# Mechanical_and_Interconnect.net
KiCad netlist of a schematic drawn in Altium Designer
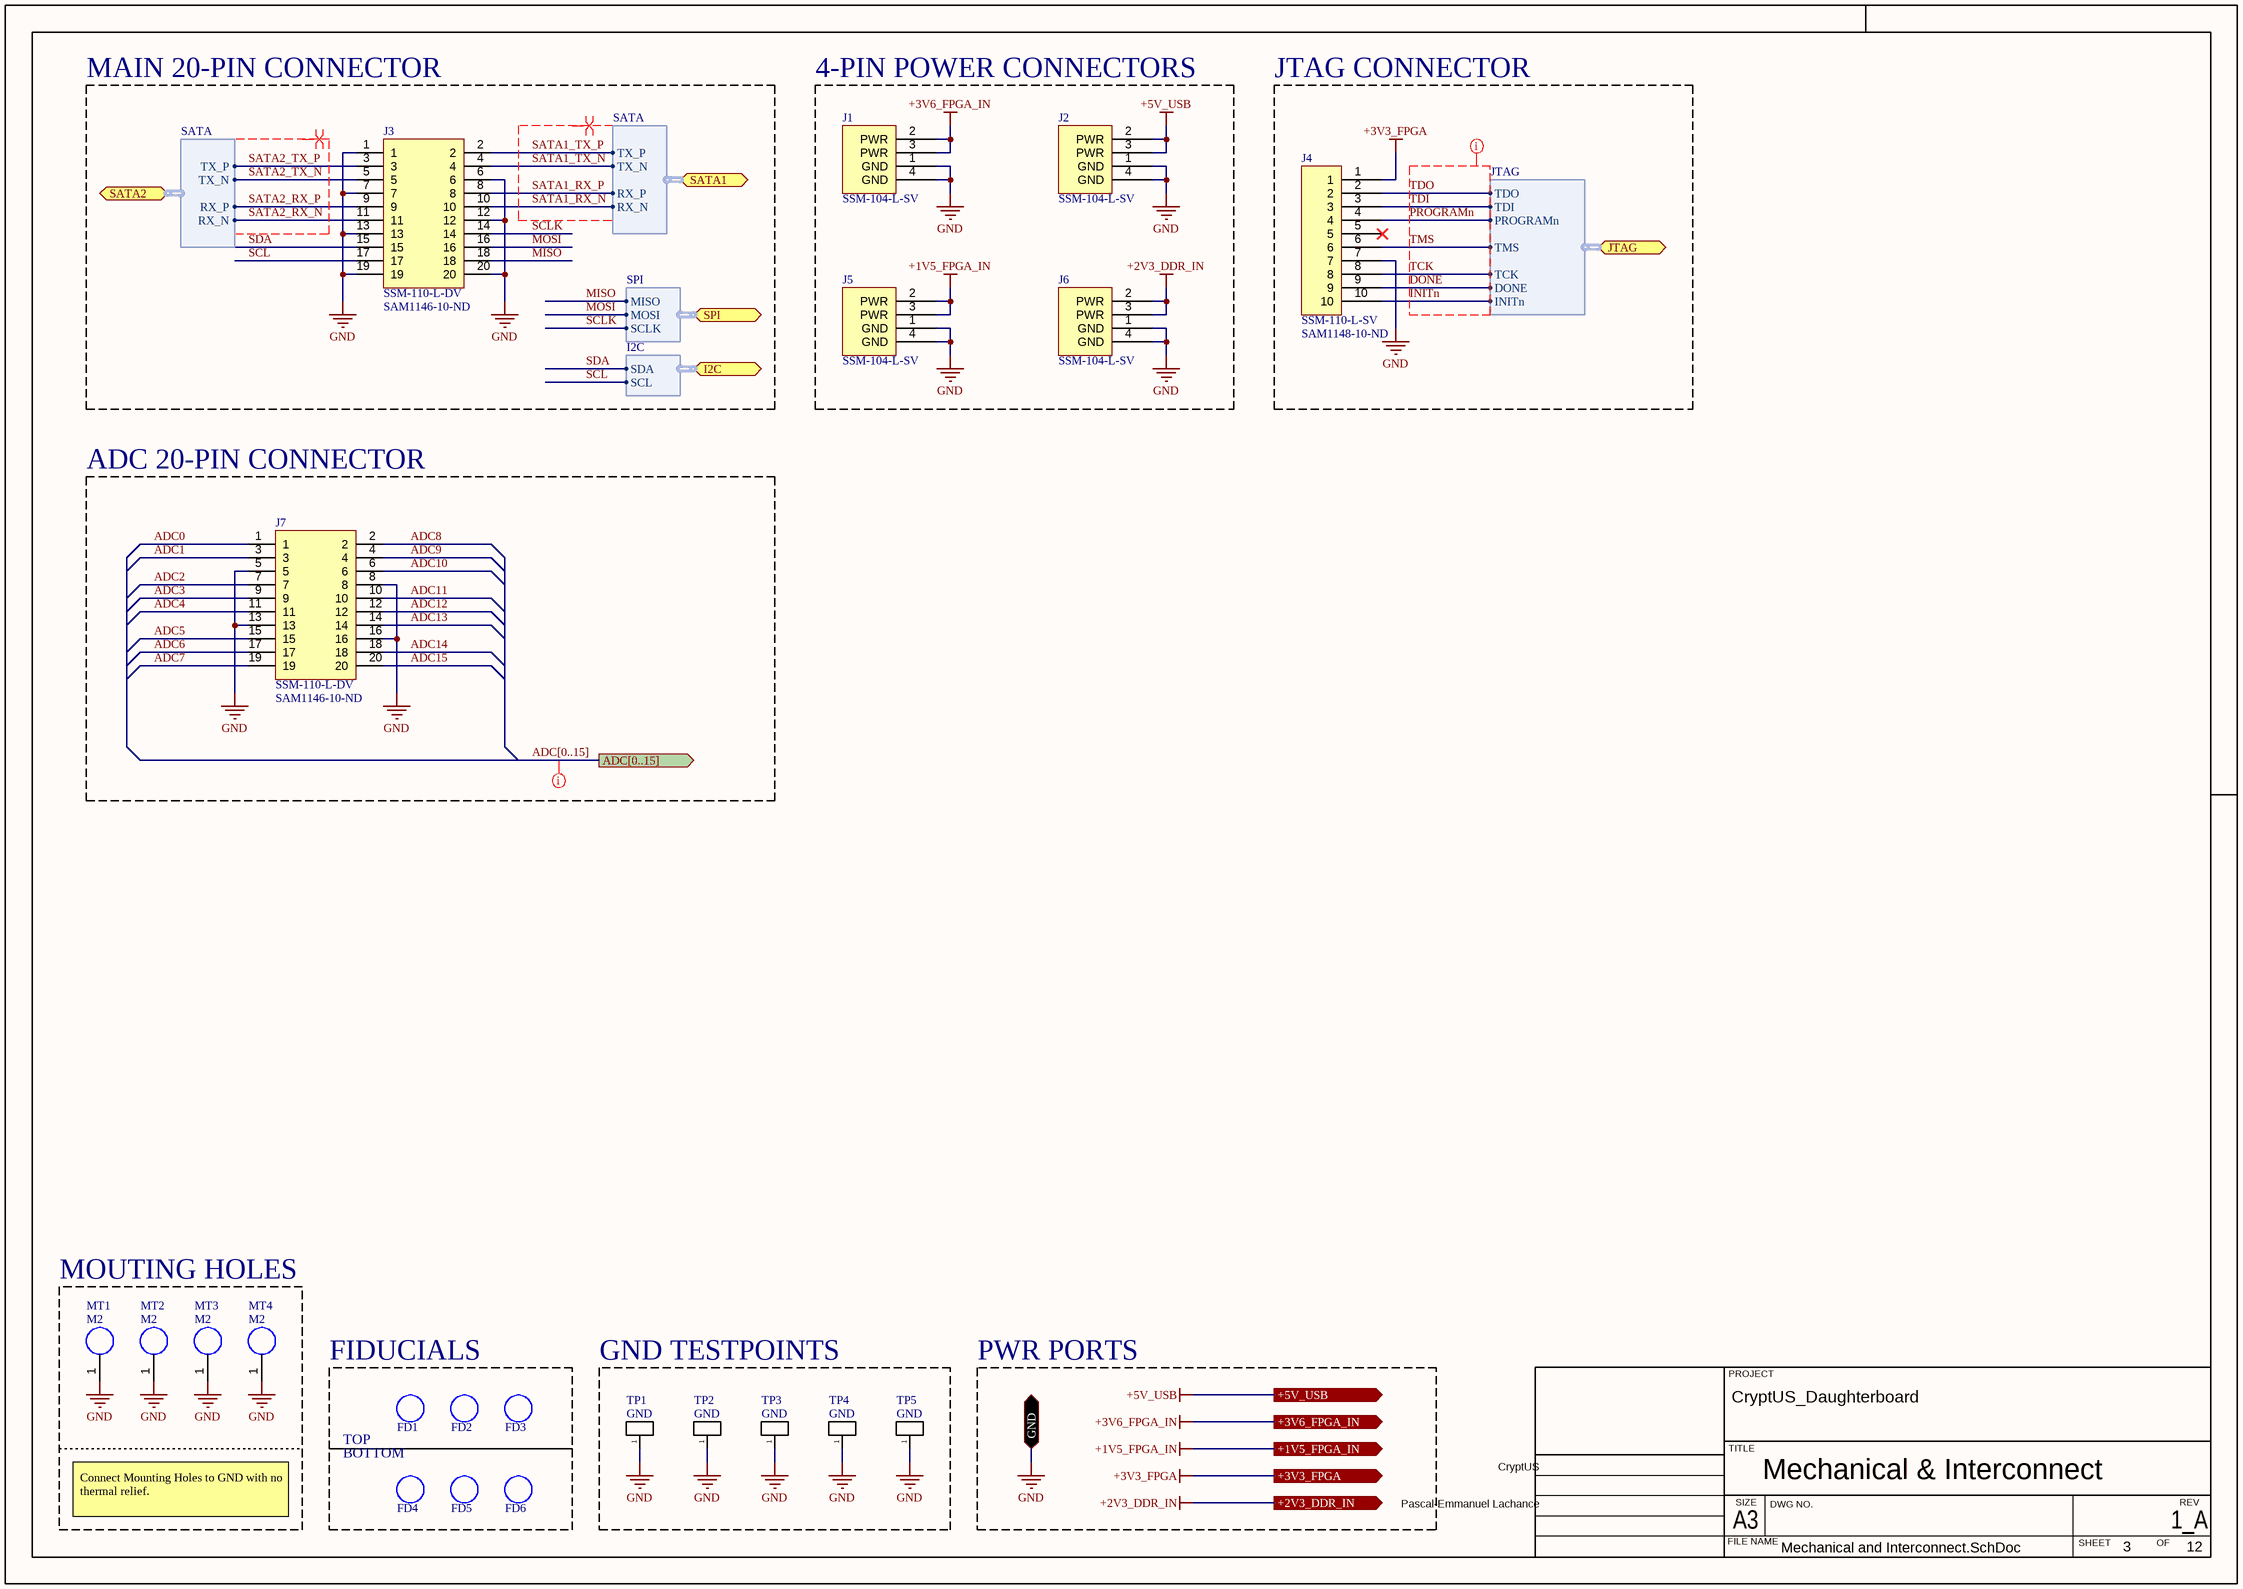
[diagram p0: Mechanical and Interconnect.SchDoc]

(export (version "E")
  (design (tool "Eeschema 10.0.6"))
  (components
    (comp (ref "FD1") (value "FIDUCIAL") (footprint "FIDUCIAL") (libsource (lib "Symbols") (part "FIDUCIAL")))
    (comp (ref "FD2") (value "FIDUCIAL") (footprint "FIDUCIAL") (libsource (lib "Symbols") (part "FIDUCIAL")))
    (comp (ref "FD3") (value "FIDUCIAL") (footprint "FIDUCIAL") (libsource (lib "Symbols") (part "FIDUCIAL")))
    (comp (ref "FD4") (value "FIDUCIAL") (footprint "FIDUCIAL") (libsource (lib "Symbols") (part "FIDUCIAL")))
    (comp (ref "FD5") (value "FIDUCIAL") (footprint "FIDUCIAL") (libsource (lib "Symbols") (part "FIDUCIAL")))
    (comp (ref "FD6") (value "FIDUCIAL") (footprint "FIDUCIAL") (libsource (lib "Symbols") (part "FIDUCIAL")))
    (comp (ref "J1")
      (value "SSM-104-L-SV")
      (footprint "SSM-104-L-SV")
      (description "CONN RCPT 4POS 0.1 GOLD SMD")
      (fields (field (name "MFR") "Samtec Inc."))
      (libsource (lib "CryptLib") (part "CONN_SSM-104-L-SV"))
    )
    (comp (ref "J2")
      (value "SSM-104-L-SV")
      (footprint "CryptLib:SSM-104-L-SV")
      (description "CONN RCPT 4POS 0.1 GOLD SMD")
      (fields (field (name "MFR") "Samtec Inc."))
      (libsource (lib "CryptLib") (part "CONN_SSM-104-L-SV"))
    )
    (comp (ref "J3")
      (value "SSM-110-L-DV")
      (footprint "SSM-110-L-DV")
      (fields (field (name "MFR") "Samtech Inc.") (field (name "SUPPLIER PART NUMBER 1") "SAM1146-10-ND"))
      (libsource (lib "CryptLib") (part "CONN_SSM-110-L-DV"))
    )
    (comp (ref "J4")
      (value "SSM-110-L-SV")
      (footprint "SSM-110-L-SV")
      (description "CONN RCPT 10POS 0.1 GOLD SMD")
      (fields (field (name "MFR") "Samtec Inc.") (field (name "SUPPLIER PART NUMBER 1") "SAM1148-10-ND"))
      (libsource (lib "CryptLib") (part "CONN_SSM-110-L-SV"))
    )
    (comp (ref "J5")
      (value "SSM-104-L-SV")
      (footprint "SSM-104-L-SV")
      (description "CONN RCPT 4POS 0.1 GOLD SMD")
      (fields (field (name "MFR") "Samtec Inc."))
      (libsource (lib "CryptLib") (part "CONN_SSM-104-L-SV"))
    )
    (comp (ref "J6")
      (value "SSM-104-L-SV")
      (footprint "SSM-104-L-SV")
      (description "CONN RCPT 4POS 0.1 GOLD SMD")
      (fields (field (name "MFR") "Samtec Inc."))
      (libsource (lib "CryptLib") (part "CONN_SSM-104-L-SV"))
    )
    (comp (ref "J7")
      (value "SSM-110-L-DV")
      (footprint "SSM-110-L-DV")
      (fields (field (name "MFR") "Samtech Inc.") (field (name "SUPPLIER PART NUMBER 1") "SAM1146-10-ND"))
      (libsource (lib "CryptLib") (part "CONN_SSM-110-L-DV"))
    )
    (comp (ref "MT1") (value "M2") (footprint "MTH_M2") (libsource (lib "RaesLib") (part "MOUNTING_HOLE")))
    (comp (ref "MT2") (value "M2") (footprint "MTH_M2") (libsource (lib "RaesLib") (part "MOUNTING_HOLE")))
    (comp (ref "MT3") (value "M2") (footprint "MTH_M2") (libsource (lib "RaesLib") (part "MOUNTING_HOLE")))
    (comp (ref "MT4") (value "M2") (footprint "MTH_M2") (libsource (lib "RaesLib") (part "MOUNTING_HOLE")))
    (comp (ref "TP1")
      (value "GND")
      (footprint "TP_HOLE")
      (description "Test Point")
      (libsource (lib "Symbols") (part "TESTPOINT"))
    )
    (comp (ref "TP2")
      (value "GND")
      (footprint "TP_HOLE")
      (description "Test Point")
      (libsource (lib "Symbols") (part "TESTPOINT"))
    )
    (comp (ref "TP3")
      (value "GND")
      (footprint "TP_HOLE")
      (description "Test Point")
      (libsource (lib "Symbols") (part "TESTPOINT"))
    )
    (comp (ref "TP4")
      (value "GND")
      (footprint "TP_HOLE")
      (description "Test Point")
      (libsource (lib "Symbols") (part "TESTPOINT"))
    )
    (comp (ref "TP5")
      (value "GND")
      (footprint "TP_HOLE")
      (description "Test Point")
      (libsource (lib "Symbols") (part "TESTPOINT"))
    )
  )
  (nets
    (net (code "5") (name "+1V5_FPGA_IN") (class "Default")
      (node (ref "J5") (pin "2") (pinfunction "PWR_2") (pintype "power_in"))
      (node (ref "J5") (pin "3") (pinfunction "PWR_3") (pintype "power_in"))
    )
    (net (code "6") (name "+2V3_DDR_IN") (class "Default")
      (node (ref "J6") (pin "2") (pinfunction "PWR_2") (pintype "power_in"))
      (node (ref "J6") (pin "3") (pinfunction "PWR_3") (pintype "power_in"))
    )
    (net (code "7") (name "+3V3_FPGA") (class "Default")
      (node (ref "J4") (pin "1") (pinfunction "1_1") (pintype "passive"))
    )
    (net (code "8") (name "+3V6_FPGA_IN") (class "Default")
      (node (ref "J1") (pin "2") (pinfunction "PWR_2") (pintype "power_in"))
      (node (ref "J1") (pin "3") (pinfunction "PWR_3") (pintype "power_in"))
    )
    (net (code "9") (name "+5V_USB") (class "Default")
      (node (ref "J2") (pin "2") (pinfunction "PWR_2") (pintype "power_in"))
      (node (ref "J2") (pin "3") (pinfunction "PWR_3") (pintype "power_in"))
    )
    (net (code "10") (name "/ADC0") (class "Default")
      (node (ref "J7") (pin "1") (pinfunction "1_1") (pintype "passive"))
    )
    (net (code "11") (name "/ADC1") (class "Default")
      (node (ref "J7") (pin "3") (pinfunction "3_3") (pintype "passive"))
    )
    (net (code "12") (name "/ADC2") (class "Default")
      (node (ref "J7") (pin "7") (pinfunction "7_7") (pintype "passive"))
    )
    (net (code "13") (name "/ADC3") (class "Default")
      (node (ref "J7") (pin "9") (pinfunction "9_9") (pintype "passive"))
    )
    (net (code "14") (name "/ADC4") (class "Default")
      (node (ref "J7") (pin "11") (pinfunction "11_11") (pintype "passive"))
    )
    (net (code "15") (name "/ADC5") (class "Default")
      (node (ref "J7") (pin "15") (pinfunction "15_15") (pintype "passive"))
    )
    (net (code "16") (name "/ADC6") (class "Default")
      (node (ref "J7") (pin "17") (pinfunction "17_17") (pintype "passive"))
    )
    (net (code "17") (name "/ADC7") (class "Default")
      (node (ref "J7") (pin "19") (pinfunction "19_19") (pintype "passive"))
    )
    (net (code "18") (name "/ADC8") (class "Default")
      (node (ref "J7") (pin "2") (pinfunction "2_2") (pintype "passive"))
    )
    (net (code "19") (name "/ADC9") (class "Default")
      (node (ref "J7") (pin "4") (pinfunction "4_4") (pintype "passive"))
    )
    (net (code "20") (name "/ADC10") (class "Default")
      (node (ref "J7") (pin "6") (pinfunction "6_6") (pintype "passive"))
    )
    (net (code "21") (name "/ADC11") (class "Default")
      (node (ref "J7") (pin "10") (pinfunction "10_10") (pintype "passive"))
    )
    (net (code "22") (name "/ADC12") (class "Default")
      (node (ref "J7") (pin "12") (pinfunction "12_12") (pintype "passive"))
    )
    (net (code "23") (name "/ADC13") (class "Default")
      (node (ref "J7") (pin "14") (pinfunction "14_14") (pintype "passive"))
    )
    (net (code "24") (name "/ADC14") (class "Default")
      (node (ref "J7") (pin "18") (pinfunction "18_18") (pintype "passive"))
    )
    (net (code "25") (name "/ADC15") (class "Default")
      (node (ref "J7") (pin "20") (pinfunction "20_20") (pintype "passive"))
    )
    (net (code "27") (name "/DONE") (class "Default")
      (node (ref "J4") (pin "9") (pinfunction "9_9") (pintype "passive"))
    )
    (net (code "28") (name "/INITn") (class "Default")
      (node (ref "J4") (pin "10") (pinfunction "10_10") (pintype "passive"))
    )
    (net (code "29") (name "/MISO") (class "Default")
      (node (ref "J3") (pin "18") (pinfunction "18_18") (pintype "passive"))
    )
    (net (code "30") (name "/MOSI") (class "Default")
      (node (ref "J3") (pin "16") (pinfunction "16_16") (pintype "passive"))
    )
    (net (code "31") (name "/PROGRAMn") (class "Default")
      (node (ref "J4") (pin "4") (pinfunction "4_4") (pintype "passive"))
    )
    (net (code "32") (name "/SATA1_RX_N") (class "Default")
      (node (ref "J3") (pin "10") (pinfunction "10_10") (pintype "passive"))
    )
    (net (code "33") (name "/SATA1_RX_P") (class "Default")
      (node (ref "J3") (pin "8") (pinfunction "8_8") (pintype "passive"))
    )
    (net (code "34") (name "/SATA1_TX_N") (class "Default")
      (node (ref "J3") (pin "4") (pinfunction "4_4") (pintype "passive"))
    )
    (net (code "35") (name "/SATA1_TX_P") (class "Default")
      (node (ref "J3") (pin "2") (pinfunction "2_2") (pintype "passive"))
    )
    (net (code "36") (name "/SATA2_RX_N") (class "Default")
      (node (ref "J3") (pin "11") (pinfunction "11_11") (pintype "passive"))
    )
    (net (code "37") (name "/SATA2_RX_P") (class "Default")
      (node (ref "J3") (pin "9") (pinfunction "9_9") (pintype "passive"))
    )
    (net (code "38") (name "/SATA2_TX_N") (class "Default")
      (node (ref "J3") (pin "5") (pinfunction "5_5") (pintype "passive"))
    )
    (net (code "39") (name "/SATA2_TX_P") (class "Default")
      (node (ref "J3") (pin "3") (pinfunction "3_3") (pintype "passive"))
    )
    (net (code "40") (name "/SCL") (class "Default")
      (node (ref "J3") (pin "17") (pinfunction "17_17") (pintype "passive"))
    )
    (net (code "41") (name "/SCLK") (class "Default")
      (node (ref "J3") (pin "14") (pinfunction "14_14") (pintype "passive"))
    )
    (net (code "42") (name "/SDA") (class "Default")
      (node (ref "J3") (pin "15") (pinfunction "15_15") (pintype "passive"))
    )
    (net (code "43") (name "/TCK") (class "Default")
      (node (ref "J4") (pin "8") (pinfunction "8_8") (pintype "passive"))
    )
    (net (code "44") (name "/TDI") (class "Default")
      (node (ref "J4") (pin "3") (pinfunction "3_3") (pintype "passive"))
    )
    (net (code "45") (name "/TDO") (class "Default")
      (node (ref "J4") (pin "2") (pinfunction "2_2") (pintype "passive"))
    )
    (net (code "46") (name "/TMS") (class "Default")
      (node (ref "J4") (pin "6") (pinfunction "6_6") (pintype "passive"))
    )
    (net (code "51") (name "GND") (class "Default")
      (node (ref "J1") (pin "1") (pinfunction "GND_1") (pintype "power_in"))
      (node (ref "J1") (pin "4") (pinfunction "GND_4") (pintype "power_in"))
      (node (ref "J2") (pin "1") (pinfunction "GND_1") (pintype "power_in"))
      (node (ref "J2") (pin "4") (pinfunction "GND_4") (pintype "power_in"))
      (node (ref "J3") (pin "1") (pinfunction "1_1") (pintype "passive"))
      (node (ref "J3") (pin "12") (pinfunction "12_12") (pintype "passive"))
      (node (ref "J3") (pin "13") (pinfunction "13_13") (pintype "passive"))
      (node (ref "J3") (pin "19") (pinfunction "19_19") (pintype "passive"))
      (node (ref "J3") (pin "20") (pinfunction "20_20") (pintype "passive"))
      (node (ref "J3") (pin "6") (pinfunction "6_6") (pintype "passive"))
      (node (ref "J3") (pin "7") (pinfunction "7_7") (pintype "passive"))
      (node (ref "J4") (pin "7") (pinfunction "7_7") (pintype "passive"))
      (node (ref "J5") (pin "1") (pinfunction "GND_1") (pintype "power_in"))
      (node (ref "J5") (pin "4") (pinfunction "GND_4") (pintype "power_in"))
      (node (ref "J6") (pin "1") (pinfunction "GND_1") (pintype "power_in"))
      (node (ref "J6") (pin "4") (pinfunction "GND_4") (pintype "power_in"))
      (node (ref "J7") (pin "13") (pinfunction "13_13") (pintype "passive"))
      (node (ref "J7") (pin "16") (pinfunction "16_16") (pintype "passive"))
      (node (ref "J7") (pin "5") (pinfunction "5_5") (pintype "passive"))
      (node (ref "J7") (pin "8") (pinfunction "8_8") (pintype "passive"))
      (node (ref "MT1") (pin "1") (pintype "passive"))
      (node (ref "MT2") (pin "1") (pintype "passive"))
      (node (ref "MT3") (pin "1") (pintype "passive"))
      (node (ref "MT4") (pin "1") (pintype "passive"))
      (node (ref "TP1") (pin "1") (pinfunction "A_1") (pintype "passive"))
      (node (ref "TP2") (pin "1") (pinfunction "A_1") (pintype "passive"))
      (node (ref "TP3") (pin "1") (pinfunction "A_1") (pintype "passive"))
      (node (ref "TP4") (pin "1") (pinfunction "A_1") (pintype "passive"))
      (node (ref "TP5") (pin "1") (pinfunction "A_1") (pintype "passive"))
    )
    (net (code "52") (name "unconnected-(J4-Pad5)") (class "Default")
      (node (ref "J4") (pin "5") (pinfunction "5_5") (pintype "passive+no_connect"))
    )
  )
)
